# STM32.net
KiCad netlist of a schematic drawn in Altium Designer
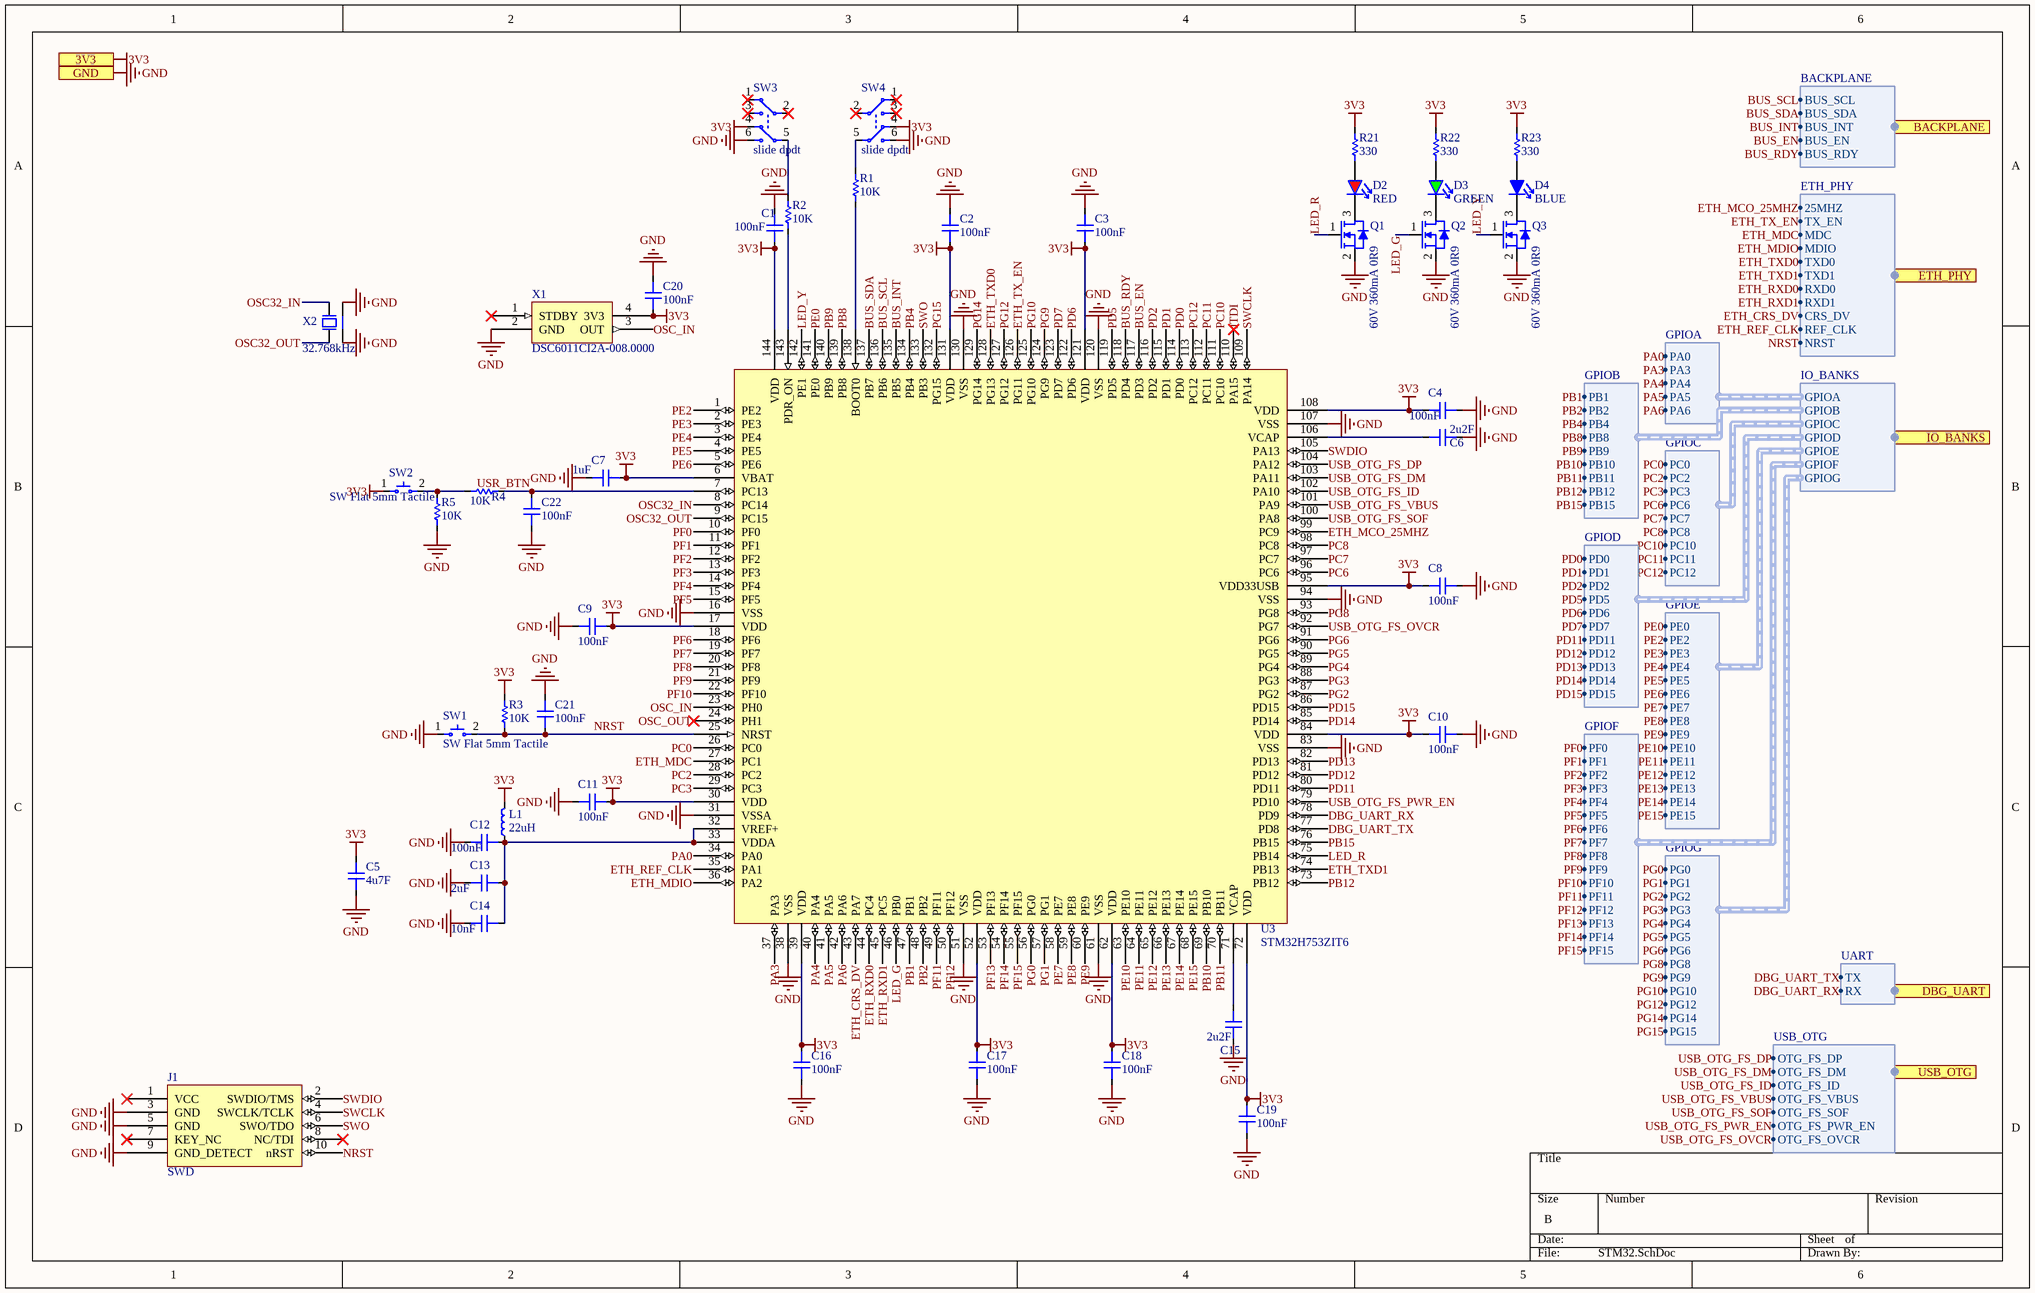
[diagram p0: STM32.SchDoc]

(export (version "E")
  (design (tool "Eeschema 10.0.6"))
  (components
    (comp (ref "C1")
      (value "100nF")
      (footprint "CAP 0805 L")
      (description "CAP 0805")
      (libsource (lib "streetbot") (part "CAP 0805"))
    )
    (comp (ref "C2")
      (value "100nF")
      (footprint "CAP 0805 L")
      (description "CAP 0805")
      (libsource (lib "streetbot") (part "CAP 0805"))
    )
    (comp (ref "C3")
      (value "100nF")
      (footprint "CAP 0805 L")
      (description "CAP 0805")
      (libsource (lib "streetbot") (part "CAP 0805"))
    )
    (comp (ref "C4")
      (value "100nF")
      (footprint "CAP 0805 L")
      (description "CAP 0805")
      (libsource (lib "streetbot") (part "CAP 0805"))
    )
    (comp (ref "C5")
      (value "4u7F")
      (footprint "CAP 0805 L")
      (description "CAP 0805")
      (libsource (lib "streetbot") (part "CAP 0805"))
    )
    (comp (ref "C6")
      (value "2u2F")
      (footprint "CAP 0805 L")
      (description "CAP 0805")
      (libsource (lib "streetbot") (part "CAP 0805"))
    )
    (comp (ref "C7")
      (value "1uF")
      (footprint "CAP 0805 L")
      (description "CAP 0805")
      (libsource (lib "streetbot") (part "CAP 0805"))
    )
    (comp (ref "C8")
      (value "100nF")
      (footprint "CAP 0805 L")
      (description "CAP 0805")
      (libsource (lib "streetbot") (part "CAP 0805"))
    )
    (comp (ref "C9")
      (value "100nF")
      (footprint "CAP 0805 L")
      (description "CAP 0805")
      (libsource (lib "streetbot") (part "CAP 0805"))
    )
    (comp (ref "C10")
      (value "100nF")
      (footprint "CAP 0805 L")
      (description "CAP 0805")
      (libsource (lib "streetbot") (part "CAP 0805"))
    )
    (comp (ref "C11")
      (value "100nF")
      (footprint "CAP 0805 L")
      (description "CAP 0805")
      (libsource (lib "streetbot") (part "CAP 0805"))
    )
    (comp (ref "C12")
      (value "100nF")
      (footprint "CAP 0805 L")
      (description "CAP 0805")
      (libsource (lib "streetbot") (part "CAP 0805"))
    )
    (comp (ref "C13")
      (value "2uF")
      (footprint "CAP 0805 L")
      (description "CAP 0805")
      (libsource (lib "streetbot") (part "CAP 0805"))
    )
    (comp (ref "C14")
      (value "10nF")
      (footprint "CAP 0805 L")
      (description "CAP 0805")
      (libsource (lib "streetbot") (part "CAP 0805"))
    )
    (comp (ref "C15")
      (value "2u2F")
      (footprint "CAP 0805 L")
      (description "CAP 0805")
      (libsource (lib "streetbot") (part "CAP 0805"))
    )
    (comp (ref "C16")
      (value "100nF")
      (footprint "CAP 0805 L")
      (description "CAP 0805")
      (libsource (lib "streetbot") (part "CAP 0805"))
    )
    (comp (ref "C17")
      (value "100nF")
      (footprint "CAP 0805 L")
      (description "CAP 0805")
      (libsource (lib "streetbot") (part "CAP 0805"))
    )
    (comp (ref "C18")
      (value "100nF")
      (footprint "CAP 0805 L")
      (description "CAP 0805")
      (libsource (lib "streetbot") (part "CAP 0805"))
    )
    (comp (ref "C19")
      (value "100nF")
      (footprint "CAP 0805 L")
      (description "CAP 0805")
      (libsource (lib "streetbot") (part "CAP 0805"))
    )
    (comp (ref "C20")
      (value "100nF")
      (footprint "CAP 0805 L")
      (description "CAP 0805")
      (libsource (lib "streetbot") (part "CAP 0805"))
    )
    (comp (ref "C21")
      (value "100nF")
      (footprint "CAP 0805 L")
      (description "CAP 0805")
      (libsource (lib "streetbot") (part "CAP 0805"))
    )
    (comp (ref "C22")
      (value "100nF")
      (footprint "CAP 0805 L")
      (description "CAP 0805")
      (libsource (lib "streetbot") (part "CAP 0805"))
    )
    (comp (ref "D2")
      (value "RED")
      (footprint "LED 0603 RED")
      (libsource (lib "streetbot") (part "LED 0603 RED"))
    )
    (comp (ref "D3")
      (value "GREEN")
      (footprint "LED 0603 GREEN")
      (libsource (lib "streetbot") (part "LED 0603 GREEN"))
    )
    (comp (ref "D4")
      (value "BLUE")
      (footprint "LED 0603 BLUE")
      (libsource (lib "streetbot") (part "LED 0603 BLUE"))
    )
    (comp (ref "J1")
      (value "SWD")
      (footprint "CONN IDC 10P P0.05")
      (description "CONN SWD IDC 0.05")
      (libsource (lib "streetbot") (part "CONN SWD IDC 0.05"))
    )
    (comp (ref "L1")
      (value "22uH")
      (footprint "IND 0805 L")
      (description "IND 0805")
      (libsource (lib "streetbot") (part "IND 0805"))
    )
    (comp (ref "Q1")
      (value "60V 360mA 0R9")
      (footprint "SOT23")
      (description "PMN20ENAX")
      (libsource (lib "streetbot") (part "FET 60V 360mA 0R9"))
    )
    (comp (ref "Q2")
      (value "60V 360mA 0R9")
      (footprint "SOT23")
      (description "PMN20ENAX")
      (libsource (lib "streetbot") (part "FET 60V 360mA 0R9"))
    )
    (comp (ref "Q3")
      (value "60V 360mA 0R9")
      (footprint "SOT23")
      (description "PMN20ENAX")
      (libsource (lib "streetbot") (part "FET 60V 360mA 0R9"))
    )
    (comp (ref "R1")
      (value "10K")
      (footprint "RES 0603 L")
      (description "RES 0603")
      (libsource (lib "streetbot") (part "RES 0603"))
    )
    (comp (ref "R2")
      (value "10K")
      (footprint "RES 0603 L")
      (description "RES 0603")
      (libsource (lib "streetbot") (part "RES 0603"))
    )
    (comp (ref "R3")
      (value "10K")
      (footprint "RES 0603 L")
      (description "RES 0603")
      (libsource (lib "streetbot") (part "RES 0603"))
    )
    (comp (ref "R4")
      (value "10K")
      (footprint "RES 0603 L")
      (description "RES 0603")
      (libsource (lib "streetbot") (part "RES 0603"))
    )
    (comp (ref "R5")
      (value "10K")
      (footprint "RES 0603 L")
      (description "RES 0603")
      (libsource (lib "streetbot") (part "RES 0603"))
    )
    (comp (ref "R21")
      (value "330")
      (footprint "RES 0603 L")
      (description "RES 0603")
      (libsource (lib "streetbot") (part "RES 0603"))
    )
    (comp (ref "R22")
      (value "330")
      (footprint "RES 0603 L")
      (description "RES 0603")
      (libsource (lib "streetbot") (part "RES 0603"))
    )
    (comp (ref "R23")
      (value "330")
      (footprint "RES 0603 L")
      (description "RES 0603")
      (libsource (lib "streetbot") (part "RES 0603"))
    )
    (comp (ref "SW1")
      (value "SW Flat 5mm Tactile")
      (footprint "SW 5MM TACTILE")
      (libsource (lib "streetbot") (part "SW Flat 5mm Tactile"))
    )
    (comp (ref "SW2")
      (value "SW Flat 5mm Tactile")
      (footprint "SW 5MM TACTILE")
      (libsource (lib "streetbot") (part "SW Flat 5mm Tactile"))
    )
    (comp (ref "SW3")
      (value "slide dpdt")
      (footprint "SW SIDE SLIDE DPDT")
      (description "JS202011JAQN")
      (libsource (lib "streetbot") (part "SW horz slide dpdt"))
    )
    (comp (ref "SW4")
      (value "slide dpdt")
      (footprint "SW SIDE SLIDE DPDT")
      (description "JS202011JAQN")
      (libsource (lib "streetbot") (part "SW horz slide dpdt"))
    )
    (comp (ref "U3")
      (value "STM32H753ZIT6")
      (footprint "LQFP144")
      (libsource (lib "streetbot") (part "STM32H753ZIT6"))
    )
    (comp (ref "X1")
      (value "DSC6011CI2A-008.0000")
      (footprint "XO 3.2x2.5")
      (libsource (lib "streetbot") (part "XO MEMS 8MHz"))
    )
    (comp (ref "X2")
      (value "32.768kHz")
      (footprint "XTAL 8.0x3.8")
      (description "RSM200S-32.768-12.5-10PPM-NPB")
      (libsource (lib "streetbot") (part "XTAL 32.768kHz"))
    )
  )
  (nets
    (net (code "12") (name "/BUS_EN") (class "Default")
      (node (ref "U3") (pin "117") (pinfunction "PD3_117") (pintype "bidirectional"))
    )
    (net (code "13") (name "/BUS_INT") (class "Default")
      (node (ref "U3") (pin "135") (pinfunction "PB5_135") (pintype "bidirectional"))
    )
    (net (code "14") (name "/BUS_RDY") (class "Default")
      (node (ref "U3") (pin "118") (pinfunction "PD4_118") (pintype "bidirectional"))
    )
    (net (code "15") (name "/BUS_SCL") (class "Default")
      (node (ref "U3") (pin "136") (pinfunction "PB6_136") (pintype "bidirectional"))
    )
    (net (code "16") (name "/BUS_SDA") (class "Default")
      (node (ref "U3") (pin "137") (pinfunction "PB7_137") (pintype "bidirectional"))
    )
    (net (code "17") (name "/DBG_UART_RX") (class "Default")
      (node (ref "U3") (pin "78") (pinfunction "PD9_78") (pintype "bidirectional"))
    )
    (net (code "18") (name "/DBG_UART_TX") (class "Default")
      (node (ref "U3") (pin "77") (pinfunction "PD8_77") (pintype "bidirectional"))
    )
    (net (code "19") (name "/ETH_CRS_DV") (class "Default")
      (node (ref "U3") (pin "43") (pinfunction "PA7_43") (pintype "bidirectional"))
    )
    (net (code "20") (name "/ETH_MCO_25MHZ") (class "Default")
      (node (ref "U3") (pin "99") (pinfunction "PC9_99") (pintype "bidirectional"))
    )
    (net (code "21") (name "/ETH_MDC") (class "Default")
      (node (ref "U3") (pin "27") (pinfunction "PC1_27") (pintype "bidirectional"))
    )
    (net (code "22") (name "/ETH_MDIO") (class "Default")
      (node (ref "U3") (pin "36") (pinfunction "PA2_36") (pintype "bidirectional"))
    )
    (net (code "23") (name "/ETH_REF_CLK") (class "Default")
      (node (ref "U3") (pin "35") (pinfunction "PA1_35") (pintype "bidirectional"))
    )
    (net (code "24") (name "/ETH_RXD0") (class "Default")
      (node (ref "U3") (pin "44") (pinfunction "PC4_44") (pintype "bidirectional"))
    )
    (net (code "25") (name "/ETH_RXD1") (class "Default")
      (node (ref "U3") (pin "45") (pinfunction "PC5_45") (pintype "bidirectional"))
    )
    (net (code "26") (name "/ETH_TXD0") (class "Default")
      (node (ref "U3") (pin "128") (pinfunction "PG13_128") (pintype "bidirectional"))
    )
    (net (code "27") (name "/ETH_TXD1") (class "Default")
      (node (ref "U3") (pin "74") (pinfunction "PB13_74") (pintype "bidirectional"))
    )
    (net (code "28") (name "/ETH_TX_EN") (class "Default")
      (node (ref "U3") (pin "126") (pinfunction "PG11_126") (pintype "bidirectional"))
    )
    (net (code "30") (name "/JTDI") (class "Default")
      (node (ref "U3") (pin "110") (pinfunction "PA15_110") (pintype "bidirectional+no_connect"))
    )
    (net (code "31") (name "/LED_G") (class "Default")
      (node (ref "Q2") (pin "1") (pinfunction "14_1") (pintype "passive"))
      (node (ref "U3") (pin "46") (pinfunction "PB0_46") (pintype "bidirectional"))
    )
    (net (code "32") (name "/LED_R") (class "Default")
      (node (ref "Q1") (pin "1") (pinfunction "14_1") (pintype "passive"))
      (node (ref "U3") (pin "75") (pinfunction "PB14_75") (pintype "bidirectional"))
    )
    (net (code "33") (name "/LED_Y") (class "Default")
      (node (ref "Q3") (pin "1") (pinfunction "14_1") (pintype "passive"))
      (node (ref "U3") (pin "142") (pinfunction "PE1_142") (pintype "bidirectional"))
    )
    (net (code "34") (name "/NRST") (class "Default")
      (node (ref "C21") (pin "1") (pinfunction "1_1") (pintype "passive"))
      (node (ref "J1") (pin "10") (pinfunction "nRST_10") (pintype "bidirectional"))
      (node (ref "R3") (pin "1") (pinfunction "1_1") (pintype "passive"))
      (node (ref "SW1") (pin "2") (pinfunction "2_2") (pintype "passive"))
      (node (ref "U3") (pin "25") (pinfunction "NRST_25") (pintype "input"))
    )
    (net (code "35") (name "/OSC32_IN") (class "Default")
      (node (ref "U3") (pin "8") (pinfunction "PC14_8") (pintype "bidirectional"))
      (node (ref "X2") (pin "4") (pinfunction "4_4") (pintype "passive"))
    )
    (net (code "36") (name "/OSC32_OUT") (class "Default")
      (node (ref "U3") (pin "9") (pinfunction "PC15_9") (pintype "bidirectional"))
      (node (ref "X2") (pin "1") (pinfunction "1_1") (pintype "passive"))
    )
    (net (code "37") (name "/OSC_IN") (class "Default")
      (node (ref "U3") (pin "23") (pinfunction "PH0_23") (pintype "bidirectional"))
      (node (ref "X1") (pin "3") (pinfunction "OUT_3") (pintype "output"))
    )
    (net (code "38") (name "/OSC_OUT") (class "Default")
      (node (ref "U3") (pin "24") (pinfunction "PH1_24") (pintype "bidirectional+no_connect"))
    )
    (net (code "39") (name "/PA0") (class "Default")
      (node (ref "U3") (pin "34") (pinfunction "PA0_34") (pintype "bidirectional"))
    )
    (net (code "40") (name "/PA3") (class "Default")
      (node (ref "U3") (pin "37") (pinfunction "PA3_37") (pintype "bidirectional"))
    )
    (net (code "41") (name "/PA4") (class "Default")
      (node (ref "U3") (pin "40") (pinfunction "PA4_40") (pintype "bidirectional"))
    )
    (net (code "42") (name "/PA5") (class "Default")
      (node (ref "U3") (pin "41") (pinfunction "PA5_41") (pintype "bidirectional"))
    )
    (net (code "43") (name "/PA6") (class "Default")
      (node (ref "U3") (pin "42") (pinfunction "PA6_42") (pintype "bidirectional"))
    )
    (net (code "44") (name "/PB1") (class "Default")
      (node (ref "U3") (pin "47") (pinfunction "PB1_47") (pintype "bidirectional"))
    )
    (net (code "45") (name "/PB2") (class "Default")
      (node (ref "U3") (pin "48") (pinfunction "PB2_48") (pintype "bidirectional"))
    )
    (net (code "46") (name "/PB4") (class "Default")
      (node (ref "U3") (pin "134") (pinfunction "PB4_134") (pintype "bidirectional"))
    )
    (net (code "47") (name "/PB8") (class "Default")
      (node (ref "U3") (pin "139") (pinfunction "PB8_139") (pintype "bidirectional"))
    )
    (net (code "48") (name "/PB9") (class "Default")
      (node (ref "U3") (pin "140") (pinfunction "PB9_140") (pintype "bidirectional"))
    )
    (net (code "49") (name "/PB10") (class "Default")
      (node (ref "U3") (pin "69") (pinfunction "PB10_69") (pintype "bidirectional"))
    )
    (net (code "50") (name "/PB11") (class "Default")
      (node (ref "U3") (pin "70") (pinfunction "PB11_70") (pintype "bidirectional"))
    )
    (net (code "51") (name "/PB12") (class "Default")
      (node (ref "U3") (pin "73") (pinfunction "PB12_73") (pintype "bidirectional"))
    )
    (net (code "52") (name "/PB15") (class "Default")
      (node (ref "U3") (pin "76") (pinfunction "PB15_76") (pintype "bidirectional"))
    )
    (net (code "53") (name "/PC0") (class "Default")
      (node (ref "U3") (pin "26") (pinfunction "PC0_26") (pintype "bidirectional"))
    )
    (net (code "54") (name "/PC2") (class "Default")
      (node (ref "U3") (pin "28") (pinfunction "PC2_28") (pintype "bidirectional"))
    )
    (net (code "55") (name "/PC3") (class "Default")
      (node (ref "U3") (pin "29") (pinfunction "PC3_29") (pintype "bidirectional"))
    )
    (net (code "56") (name "/PC6") (class "Default")
      (node (ref "U3") (pin "96") (pinfunction "PC6_96") (pintype "bidirectional"))
    )
    (net (code "57") (name "/PC7") (class "Default")
      (node (ref "U3") (pin "97") (pinfunction "PC7_97") (pintype "bidirectional"))
    )
    (net (code "58") (name "/PC8") (class "Default")
      (node (ref "U3") (pin "98") (pinfunction "PC8_98") (pintype "bidirectional"))
    )
    (net (code "59") (name "/PC10") (class "Default")
      (node (ref "U3") (pin "111") (pinfunction "PC10_111") (pintype "bidirectional"))
    )
    (net (code "60") (name "/PC11") (class "Default")
      (node (ref "U3") (pin "112") (pinfunction "PC11_112") (pintype "bidirectional"))
    )
    (net (code "61") (name "/PC12") (class "Default")
      (node (ref "U3") (pin "113") (pinfunction "PC12_113") (pintype "bidirectional"))
    )
    (net (code "62") (name "/PD0") (class "Default")
      (node (ref "U3") (pin "114") (pinfunction "PD0_114") (pintype "bidirectional"))
    )
    (net (code "63") (name "/PD1") (class "Default")
      (node (ref "U3") (pin "115") (pinfunction "PD1_115") (pintype "bidirectional"))
    )
    (net (code "64") (name "/PD2") (class "Default")
      (node (ref "U3") (pin "116") (pinfunction "PD2_116") (pintype "bidirectional"))
    )
    (net (code "65") (name "/PD5") (class "Default")
      (node (ref "U3") (pin "119") (pinfunction "PD5_119") (pintype "bidirectional"))
    )
    (net (code "66") (name "/PD6") (class "Default")
      (node (ref "U3") (pin "122") (pinfunction "PD6_122") (pintype "bidirectional"))
    )
    (net (code "67") (name "/PD7") (class "Default")
      (node (ref "U3") (pin "123") (pinfunction "PD7_123") (pintype "bidirectional"))
    )
    (net (code "68") (name "/PD11") (class "Default")
      (node (ref "U3") (pin "80") (pinfunction "PD11_80") (pintype "bidirectional"))
    )
    (net (code "69") (name "/PD12") (class "Default")
      (node (ref "U3") (pin "81") (pinfunction "PD12_81") (pintype "bidirectional"))
    )
    (net (code "70") (name "/PD13") (class "Default")
      (node (ref "U3") (pin "82") (pinfunction "PD13_82") (pintype "bidirectional"))
    )
    (net (code "71") (name "/PD14") (class "Default")
      (node (ref "U3") (pin "85") (pinfunction "PD14_85") (pintype "bidirectional"))
    )
    (net (code "72") (name "/PD15") (class "Default")
      (node (ref "U3") (pin "86") (pinfunction "PD15_86") (pintype "bidirectional"))
    )
    (net (code "73") (name "/PE0") (class "Default")
      (node (ref "U3") (pin "141") (pinfunction "PE0_141") (pintype "bidirectional"))
    )
    (net (code "74") (name "/PE2") (class "Default")
      (node (ref "U3") (pin "1") (pinfunction "PE2_1") (pintype "bidirectional"))
    )
    (net (code "75") (name "/PE3") (class "Default")
      (node (ref "U3") (pin "2") (pinfunction "PE3_2") (pintype "bidirectional"))
    )
    (net (code "76") (name "/PE4") (class "Default")
      (node (ref "U3") (pin "3") (pinfunction "PE4_3") (pintype "bidirectional"))
    )
    (net (code "77") (name "/PE5") (class "Default")
      (node (ref "U3") (pin "4") (pinfunction "PE5_4") (pintype "bidirectional"))
    )
    (net (code "78") (name "/PE6") (class "Default")
      (node (ref "U3") (pin "5") (pinfunction "PE6_5") (pintype "bidirectional"))
    )
    (net (code "79") (name "/PE7") (class "Default")
      (node (ref "U3") (pin "58") (pinfunction "PE7_58") (pintype "bidirectional"))
    )
    (net (code "80") (name "/PE8") (class "Default")
      (node (ref "U3") (pin "59") (pinfunction "PE8_59") (pintype "bidirectional"))
    )
    (net (code "81") (name "/PE9") (class "Default")
      (node (ref "U3") (pin "60") (pinfunction "PE9_60") (pintype "bidirectional"))
    )
    (net (code "82") (name "/PE10") (class "Default")
      (node (ref "U3") (pin "63") (pinfunction "PE10_63") (pintype "bidirectional"))
    )
    (net (code "83") (name "/PE11") (class "Default")
      (node (ref "U3") (pin "64") (pinfunction "PE11_64") (pintype "bidirectional"))
    )
    (net (code "84") (name "/PE12") (class "Default")
      (node (ref "U3") (pin "65") (pinfunction "PE12_65") (pintype "bidirectional"))
    )
    (net (code "85") (name "/PE13") (class "Default")
      (node (ref "U3") (pin "66") (pinfunction "PE13_66") (pintype "bidirectional"))
    )
    (net (code "86") (name "/PE14") (class "Default")
      (node (ref "U3") (pin "67") (pinfunction "PE14_67") (pintype "bidirectional"))
    )
    (net (code "87") (name "/PE15") (class "Default")
      (node (ref "U3") (pin "68") (pinfunction "PE15_68") (pintype "bidirectional"))
    )
    (net (code "88") (name "/PF0") (class "Default")
      (node (ref "U3") (pin "10") (pinfunction "PF0_10") (pintype "bidirectional"))
    )
    (net (code "89") (name "/PF1") (class "Default")
      (node (ref "U3") (pin "11") (pinfunction "PF1_11") (pintype "bidirectional"))
    )
    (net (code "90") (name "/PF2") (class "Default")
      (node (ref "U3") (pin "12") (pinfunction "PF2_12") (pintype "bidirectional"))
    )
    (net (code "91") (name "/PF3") (class "Default")
      (node (ref "U3") (pin "13") (pinfunction "PF3_13") (pintype "bidirectional"))
    )
    (net (code "92") (name "/PF4") (class "Default")
      (node (ref "U3") (pin "14") (pinfunction "PF4_14") (pintype "bidirectional"))
    )
    (net (code "93") (name "/PF5") (class "Default")
      (node (ref "U3") (pin "15") (pinfunction "PF5_15") (pintype "bidirectional"))
    )
    (net (code "94") (name "/PF6") (class "Default")
      (node (ref "U3") (pin "18") (pinfunction "PF6_18") (pintype "bidirectional"))
    )
    (net (code "95") (name "/PF7") (class "Default")
      (node (ref "U3") (pin "19") (pinfunction "PF7_19") (pintype "bidirectional"))
    )
    (net (code "96") (name "/PF8") (class "Default")
      (node (ref "U3") (pin "20") (pinfunction "PF8_20") (pintype "bidirectional"))
    )
    (net (code "97") (name "/PF9") (class "Default")
      (node (ref "U3") (pin "21") (pinfunction "PF9_21") (pintype "bidirectional"))
    )
    (net (code "98") (name "/PF10") (class "Default")
      (node (ref "U3") (pin "22") (pinfunction "PF10_22") (pintype "bidirectional"))
    )
    (net (code "99") (name "/PF11") (class "Default")
      (node (ref "U3") (pin "49") (pinfunction "PF11_49") (pintype "bidirectional"))
    )
    (net (code "100") (name "/PF12") (class "Default")
      (node (ref "U3") (pin "50") (pinfunction "PF12_50") (pintype "bidirectional"))
    )
    (net (code "101") (name "/PF13") (class "Default")
      (node (ref "U3") (pin "53") (pinfunction "PF13_53") (pintype "bidirectional"))
    )
    (net (code "102") (name "/PF14") (class "Default")
      (node (ref "U3") (pin "54") (pinfunction "PF14_54") (pintype "bidirectional"))
    )
    (net (code "103") (name "/PF15") (class "Default")
      (node (ref "U3") (pin "55") (pinfunction "PF15_55") (pintype "bidirectional"))
    )
    (net (code "104") (name "/PG0") (class "Default")
      (node (ref "U3") (pin "56") (pinfunction "PG0_56") (pintype "bidirectional"))
    )
    (net (code "105") (name "/PG1") (class "Default")
      (node (ref "U3") (pin "57") (pinfunction "PG1_57") (pintype "bidirectional"))
    )
    (net (code "106") (name "/PG2") (class "Default")
      (node (ref "U3") (pin "87") (pinfunction "PG2_87") (pintype "bidirectional"))
    )
    (net (code "107") (name "/PG3") (class "Default")
      (node (ref "U3") (pin "88") (pinfunction "PG3_88") (pintype "bidirectional"))
    )
    (net (code "108") (name "/PG4") (class "Default")
      (node (ref "U3") (pin "89") (pinfunction "PG4_89") (pintype "bidirectional"))
    )
    (net (code "109") (name "/PG5") (class "Default")
      (node (ref "U3") (pin "90") (pinfunction "PG5_90") (pintype "bidirectional"))
    )
    (net (code "110") (name "/PG6") (class "Default")
      (node (ref "U3") (pin "91") (pinfunction "PG6_91") (pintype "bidirectional"))
    )
    (net (code "111") (name "/PG8") (class "Default")
      (node (ref "U3") (pin "93") (pinfunction "PG8_93") (pintype "bidirectional"))
    )
    (net (code "112") (name "/PG9") (class "Default")
      (node (ref "U3") (pin "124") (pinfunction "PG9_124") (pintype "bidirectional"))
    )
    (net (code "113") (name "/PG10") (class "Default")
      (node (ref "U3") (pin "125") (pinfunction "PG10_125") (pintype "bidirectional"))
    )
    (net (code "114") (name "/PG12") (class "Default")
      (node (ref "U3") (pin "127") (pinfunction "PG12_127") (pintype "bidirectional"))
    )
    (net (code "115") (name "/PG14") (class "Default")
      (node (ref "U3") (pin "129") (pinfunction "PG14_129") (pintype "bidirectional"))
    )
    (net (code "116") (name "/PG15") (class "Default")
      (node (ref "U3") (pin "132") (pinfunction "PG15_132") (pintype "bidirectional"))
    )
    (net (code "117") (name "/SWCLK") (class "Default")
      (node (ref "J1") (pin "4") (pinfunction "SWCLK/TCLK_4") (pintype "bidirectional"))
      (node (ref "U3") (pin "109") (pinfunction "PA14_109") (pintype "bidirectional"))
    )
    (net (code "118") (name "/SWDIO") (class "Default")
      (node (ref "J1") (pin "2") (pinfunction "SWDIO/TMS_2") (pintype "bidirectional"))
      (node (ref "U3") (pin "105") (pinfunction "PA13_105") (pintype "bidirectional"))
    )
    (net (code "119") (name "/SWO") (class "Default")
      (node (ref "J1") (pin "6") (pinfunction "SWO/TDO_6") (pintype "bidirectional"))
      (node (ref "U3") (pin "133") (pinfunction "PB3_133") (pintype "bidirectional"))
    )
    (net (code "120") (name "/USB_OTG_FS_DM") (class "Default")
      (node (ref "U3") (pin "103") (pinfunction "PA11_103") (pintype "bidirectional"))
    )
    (net (code "121") (name "/USB_OTG_FS_DP") (class "Default")
      (node (ref "U3") (pin "104") (pinfunction "PA12_104") (pintype "bidirectional"))
    )
    (net (code "122") (name "/USB_OTG_FS_ID") (class "Default")
      (node (ref "U3") (pin "102") (pinfunction "PA10_102") (pintype "bidirectional"))
    )
    (net (code "123") (name "/USB_OTG_FS_OVCR") (class "Default")
      (node (ref "U3") (pin "92") (pinfunction "PG7_92") (pintype "bidirectional"))
    )
    (net (code "124") (name "/USB_OTG_FS_PWR_EN") (class "Default")
      (node (ref "U3") (pin "79") (pinfunction "PD10_79") (pintype "bidirectional"))
    )
    (net (code "125") (name "/USB_OTG_FS_SOF") (class "Default")
      (node (ref "U3") (pin "100") (pinfunction "PA8_100") (pintype "bidirectional"))
    )
    (net (code "126") (name "/USB_OTG_FS_VBUS") (class "Default")
      (node (ref "U3") (pin "101") (pinfunction "PA9_101") (pintype "bidirectional"))
    )
    (net (code "127") (name "/USR_BTN") (class "Default")
      (node (ref "C22") (pin "2") (pinfunction "2_2") (pintype "passive"))
      (node (ref "R4") (pin "1") (pinfunction "1_1") (pintype "passive"))
      (node (ref "U3") (pin "7") (pinfunction "PC13_7") (pintype "bidirectional"))
    )
    (net (code "138") (name "3V3") (class "Default")
      (node (ref "C1") (pin "1") (pinfunction "1_1") (pintype "passive"))
      (node (ref "C10") (pin "1") (pinfunction "1_1") (pintype "passive"))
      (node (ref "C11") (pin "2") (pinfunction "2_2") (pintype "passive"))
      (node (ref "C16") (pin "2") (pinfunction "2_2") (pintype "passive"))
      (node (ref "C17") (pin "2") (pinfunction "2_2") (pintype "passive"))
      (node (ref "C18") (pin "2") (pinfunction "2_2") (pintype "passive"))
      (node (ref "C19") (pin "2") (pinfunction "2_2") (pintype "passive"))
      (node (ref "C2") (pin "1") (pinfunction "1_1") (pintype "passive"))
      (node (ref "C20") (pin "1") (pinfunction "1_1") (pintype "passive"))
      (node (ref "C3") (pin "1") (pinfunction "1_1") (pintype "passive"))
      (node (ref "C4") (pin "1") (pinfunction "1_1") (pintype "passive"))
      (node (ref "C5") (pin "1") (pinfunction "1_1") (pintype "passive"))
      (node (ref "C7") (pin "2") (pinfunction "2_2") (pintype "passive"))
      (node (ref "C8") (pin "1") (pinfunction "1_1") (pintype "passive"))
      (node (ref "C9") (pin "2") (pinfunction "2_2") (pintype "passive"))
      (node (ref "L1") (pin "2") (pinfunction "2_2") (pintype "passive"))
      (node (ref "R21") (pin "2") (pinfunction "2_2") (pintype "passive"))
      (node (ref "R22") (pin "2") (pinfunction "2_2") (pintype "passive"))
      (node (ref "R23") (pin "2") (pinfunction "2_2") (pintype "passive"))
      (node (ref "R3") (pin "2") (pinfunction "2_2") (pintype "passive"))
      (node (ref "SW2") (pin "1") (pinfunction "1_1") (pintype "passive"))
      (node (ref "SW3") (pin "4") (pinfunction "4_4") (pintype "passive"))
      (node (ref "SW4") (pin "4") (pinfunction "4_4") (pintype "passive"))
      (node (ref "U3") (pin "108") (pinfunction "VDD_108") (pintype "power_in"))
      (node (ref "U3") (pin "121") (pinfunction "VDD_121") (pintype "power_in"))
      (node (ref "U3") (pin "131") (pinfunction "VDD_131") (pintype "power_in"))
      (node (ref "U3") (pin "144") (pinfunction "VDD_144") (pintype "power_in"))
      (node (ref "U3") (pin "17") (pinfunction "VDD_17") (pintype "power_in"))
      (node (ref "U3") (pin "30") (pinfunction "VDD_30") (pintype "power_in"))
      (node (ref "U3") (pin "39") (pinfunction "VDD_39") (pintype "power_in"))
      (node (ref "U3") (pin "52") (pinfunction "VDD_52") (pintype "power_in"))
      (node (ref "U3") (pin "6") (pinfunction "VBAT_6") (pintype "power_in"))
      (node (ref "U3") (pin "62") (pinfunction "VDD_62") (pintype "power_in"))
      (node (ref "U3") (pin "72") (pinfunction "VDD_72") (pintype "power_in"))
      (node (ref "U3") (pin "84") (pinfunction "VDD_84") (pintype "power_in"))
      (node (ref "U3") (pin "95") (pinfunction "VDD33USB_95") (pintype "power_in"))
      (node (ref "X1") (pin "4") (pinfunction "3V3_4") (pintype "power_in"))
    )
    (net (code "139") (name "GND") (class "Default")
      (node (ref "C1") (pin "2") (pinfunction "2_2") (pintype "passive"))
      (node (ref "C10") (pin "2") (pinfunction "2_2") (pintype "passive"))
      (node (ref "C11") (pin "1") (pinfunction "1_1") (pintype "passive"))
      (node (ref "C12") (pin "1") (pinfunction "1_1") (pintype "passive"))
      (node (ref "C13") (pin "1") (pinfunction "1_1") (pintype "passive"))
      (node (ref "C14") (pin "1") (pinfunction "1_1") (pintype "passive"))
      (node (ref "C15") (pin "1") (pinfunction "1_1") (pintype "passive"))
      (node (ref "C16") (pin "1") (pinfunction "1_1") (pintype "passive"))
      (node (ref "C17") (pin "1") (pinfunction "1_1") (pintype "passive"))
      (node (ref "C18") (pin "1") (pinfunction "1_1") (pintype "passive"))
      (node (ref "C19") (pin "1") (pinfunction "1_1") (pintype "passive"))
      (node (ref "C2") (pin "2") (pinfunction "2_2") (pintype "passive"))
      (node (ref "C20") (pin "2") (pinfunction "2_2") (pintype "passive"))
      (node (ref "C21") (pin "2") (pinfunction "2_2") (pintype "passive"))
      (node (ref "C22") (pin "1") (pinfunction "1_1") (pintype "passive"))
      (node (ref "C3") (pin "2") (pinfunction "2_2") (pintype "passive"))
      (node (ref "C4") (pin "2") (pinfunction "2_2") (pintype "passive"))
      (node (ref "C5") (pin "2") (pinfunction "2_2") (pintype "passive"))
      (node (ref "C6") (pin "2") (pinfunction "2_2") (pintype "passive"))
      (node (ref "C7") (pin "1") (pinfunction "1_1") (pintype "passive"))
      (node (ref "C8") (pin "2") (pinfunction "2_2") (pintype "passive"))
      (node (ref "C9") (pin "1") (pinfunction "1_1") (pintype "passive"))
      (node (ref "J1") (pin "3") (pinfunction "GND_3") (pintype "power_in"))
      (node (ref "J1") (pin "5") (pinfunction "GND_5") (pintype "power_in"))
      (node (ref "J1") (pin "9") (pinfunction "GND_DETECT_9") (pintype "power_in"))
      (node (ref "Q1") (pin "2") (pinfunction "2_2") (pintype "passive"))
      (node (ref "Q2") (pin "2") (pinfunction "2_2") (pintype "passive"))
      (node (ref "Q3") (pin "2") (pinfunction "2_2") (pintype "passive"))
      (node (ref "R5") (pin "1") (pinfunction "1_1") (pintype "passive"))
      (node (ref "SW1") (pin "1") (pinfunction "1_1") (pintype "passive"))
      (node (ref "SW3") (pin "6") (pinfunction "6_6") (pintype "passive"))
      (node (ref "SW4") (pin "6") (pinfunction "6_6") (pintype "passive"))
      (node (ref "U3") (pin "107") (pinfunction "VSS_107") (pintype "power_in"))
      (node (ref "U3") (pin "120") (pinfunction "VSS_120") (pintype "power_in"))
      (node (ref "U3") (pin "130") (pinfunction "VSS_130") (pintype "power_in"))
      (node (ref "U3") (pin "16") (pinfunction "VSS_16") (pintype "power_in"))
      (node (ref "U3") (pin "31") (pinfunction "VSSA_31") (pintype "power_in"))
      (node (ref "U3") (pin "38") (pinfunction "VSS_38") (pintype "power_in"))
      (node (ref "U3") (pin "51") (pinfunction "VSS_51") (pintype "power_in"))
      (node (ref "U3") (pin "61") (pinfunction "VSS_61") (pintype "power_in"))
      (node (ref "U3") (pin "83") (pinfunction "VSS_83") (pintype "power_in"))
      (node (ref "U3") (pin "94") (pinfunction "VSS_94") (pintype "power_in"))
      (node (ref "X1") (pin "2") (pinfunction "GND_2") (pintype "power_in"))
      (node (ref "X2") (pin "2") (pinfunction "2_2") (pintype "passive"))
      (node (ref "X2") (pin "3") (pinfunction "3_3") (pintype "passive"))
    )
    (net (code "140") (name "Net-(C6-Pad1)") (class "Default")
      (node (ref "C6") (pin "1") (pinfunction "1_1") (pintype "passive"))
      (node (ref "U3") (pin "106") (pinfunction "VCAP_106") (pintype "passive"))
    )
    (net (code "141") (name "Net-(C15-Pad2)") (class "Default")
      (node (ref "C15") (pin "2") (pinfunction "2_2") (pintype "passive"))
      (node (ref "U3") (pin "71") (pinfunction "VCAP_71") (pintype "passive"))
    )
    (net (code "142") (name "Net-(D2-Pad1)") (class "Default")
      (node (ref "D2") (pin "1") (pinfunction "1_1") (pintype "passive"))
      (node (ref "Q1") (pin "3") (pinfunction "3_3") (pintype "passive"))
    )
    (net (code "143") (name "Net-(D2-Pad2)") (class "Default")
      (node (ref "D2") (pin "2") (pinfunction "2_2") (pintype "passive"))
      (node (ref "R21") (pin "1") (pinfunction "1_1") (pintype "passive"))
    )
    (net (code "144") (name "Net-(D3-Pad1)") (class "Default")
      (node (ref "D3") (pin "1") (pinfunction "1_1") (pintype "passive"))
      (node (ref "Q2") (pin "3") (pinfunction "3_3") (pintype "passive"))
    )
    (net (code "145") (name "Net-(D3-Pad2)") (class "Default")
      (node (ref "D3") (pin "2") (pinfunction "2_2") (pintype "passive"))
      (node (ref "R22") (pin "1") (pinfunction "1_1") (pintype "passive"))
    )
    (net (code "146") (name "Net-(D4-Pad1)") (class "Default")
      (node (ref "D4") (pin "1") (pinfunction "1_1") (pintype "passive"))
      (node (ref "Q3") (pin "3") (pinfunction "3_3") (pintype "passive"))
    )
    (net (code "147") (name "Net-(D4-Pad2)") (class "Default")
      (node (ref "D4") (pin "2") (pinfunction "2_2") (pintype "passive"))
      (node (ref "R23") (pin "1") (pinfunction "1_1") (pintype "passive"))
    )
    (net (code "148") (name "Net-(R1-Pad2)") (class "Default")
      (node (ref "R1") (pin "2") (pinfunction "2_2") (pintype "passive"))
      (node (ref "SW4") (pin "5") (pinfunction "5_5") (pintype "passive"))
    )
    (net (code "149") (name "Net-(R2-Pad2)") (class "Default")
      (node (ref "R2") (pin "2") (pinfunction "2_2") (pintype "passive"))
      (node (ref "SW3") (pin "5") (pinfunction "5_5") (pintype "passive"))
    )
    (net (code "150") (name "Net-(R4-Pad2)") (class "Default")
      (node (ref "R4") (pin "2") (pinfunction "2_2") (pintype "passive"))
      (node (ref "R5") (pin "2") (pinfunction "2_2") (pintype "passive"))
      (node (ref "SW2") (pin "2") (pinfunction "2_2") (pintype "passive"))
    )
    (net (code "151") (name "Net-(U3-BOOT0)") (class "Default")
      (node (ref "R1") (pin "1") (pinfunction "1_1") (pintype "passive"))
      (node (ref "U3") (pin "138") (pinfunction "BOOT0_138") (pintype "input"))
    )
    (net (code "152") (name "Net-(U3-PDR_ON)") (class "Default")
      (node (ref "R2") (pin "1") (pinfunction "1_1") (pintype "passive"))
      (node (ref "U3") (pin "143") (pinfunction "PDR_ON_143") (pintype "input"))
    )
    (net (code "153") (name "Net-(U3-VDDA)") (class "Default")
      (node (ref "C12") (pin "2") (pinfunction "2_2") (pintype "passive"))
      (node (ref "C13") (pin "2") (pinfunction "2_2") (pintype "passive"))
      (node (ref "C14") (pin "2") (pinfunction "2_2") (pintype "passive"))
      (node (ref "L1") (pin "1") (pinfunction "1_1") (pintype "passive"))
      (node (ref "U3") (pin "32") (pinfunction "VREF+_32") (pintype "passive"))
      (node (ref "U3") (pin "33") (pinfunction "VDDA_33") (pintype "power_in"))
    )
    (net (code "154") (name "unconnected-(J1-KEY_NC-Pad7)") (class "Default")
      (node (ref "J1") (pin "7") (pinfunction "KEY_NC_7") (pintype "passive+no_connect"))
    )
    (net (code "155") (name "unconnected-(J1-NC{slash}TDI-Pad8)") (class "Default")
      (node (ref "J1") (pin "8") (pinfunction "NC/TDI_8") (pintype "bidirectional+no_connect"))
    )
    (net (code "156") (name "unconnected-(J1-VCC-Pad1)") (class "Default")
      (node (ref "J1") (pin "1") (pinfunction "VCC_1") (pintype "power_in+no_connect"))
    )
    (net (code "157") (name "unconnected-(SW3-Pad1)") (class "Default")
      (node (ref "SW3") (pin "1") (pinfunction "1_1") (pintype "passive+no_connect"))
    )
    (net (code "158") (name "unconnected-(SW3-Pad2)") (class "Default")
      (node (ref "SW3") (pin "2") (pinfunction "2_2") (pintype "passive+no_connect"))
    )
    (net (code "159") (name "unconnected-(SW3-Pad3)") (class "Default")
      (node (ref "SW3") (pin "3") (pinfunction "3_3") (pintype "passive+no_connect"))
    )
    (net (code "160") (name "unconnected-(SW4-Pad1)") (class "Default")
      (node (ref "SW4") (pin "1") (pinfunction "1_1") (pintype "passive+no_connect"))
    )
    (net (code "161") (name "unconnected-(SW4-Pad2)") (class "Default")
      (node (ref "SW4") (pin "2") (pinfunction "2_2") (pintype "passive+no_connect"))
    )
    (net (code "162") (name "unconnected-(SW4-Pad3)") (class "Default")
      (node (ref "SW4") (pin "3") (pinfunction "3_3") (pintype "passive+no_connect"))
    )
    (net (code "163") (name "unconnected-(X1-STDBY-Pad1)") (class "Default")
      (node (ref "X1") (pin "1") (pinfunction "STDBY_1") (pintype "input+no_connect"))
    )
  )
)
